# Interface_Connector.net
KiCad netlist of a schematic drawn in Altium Designer
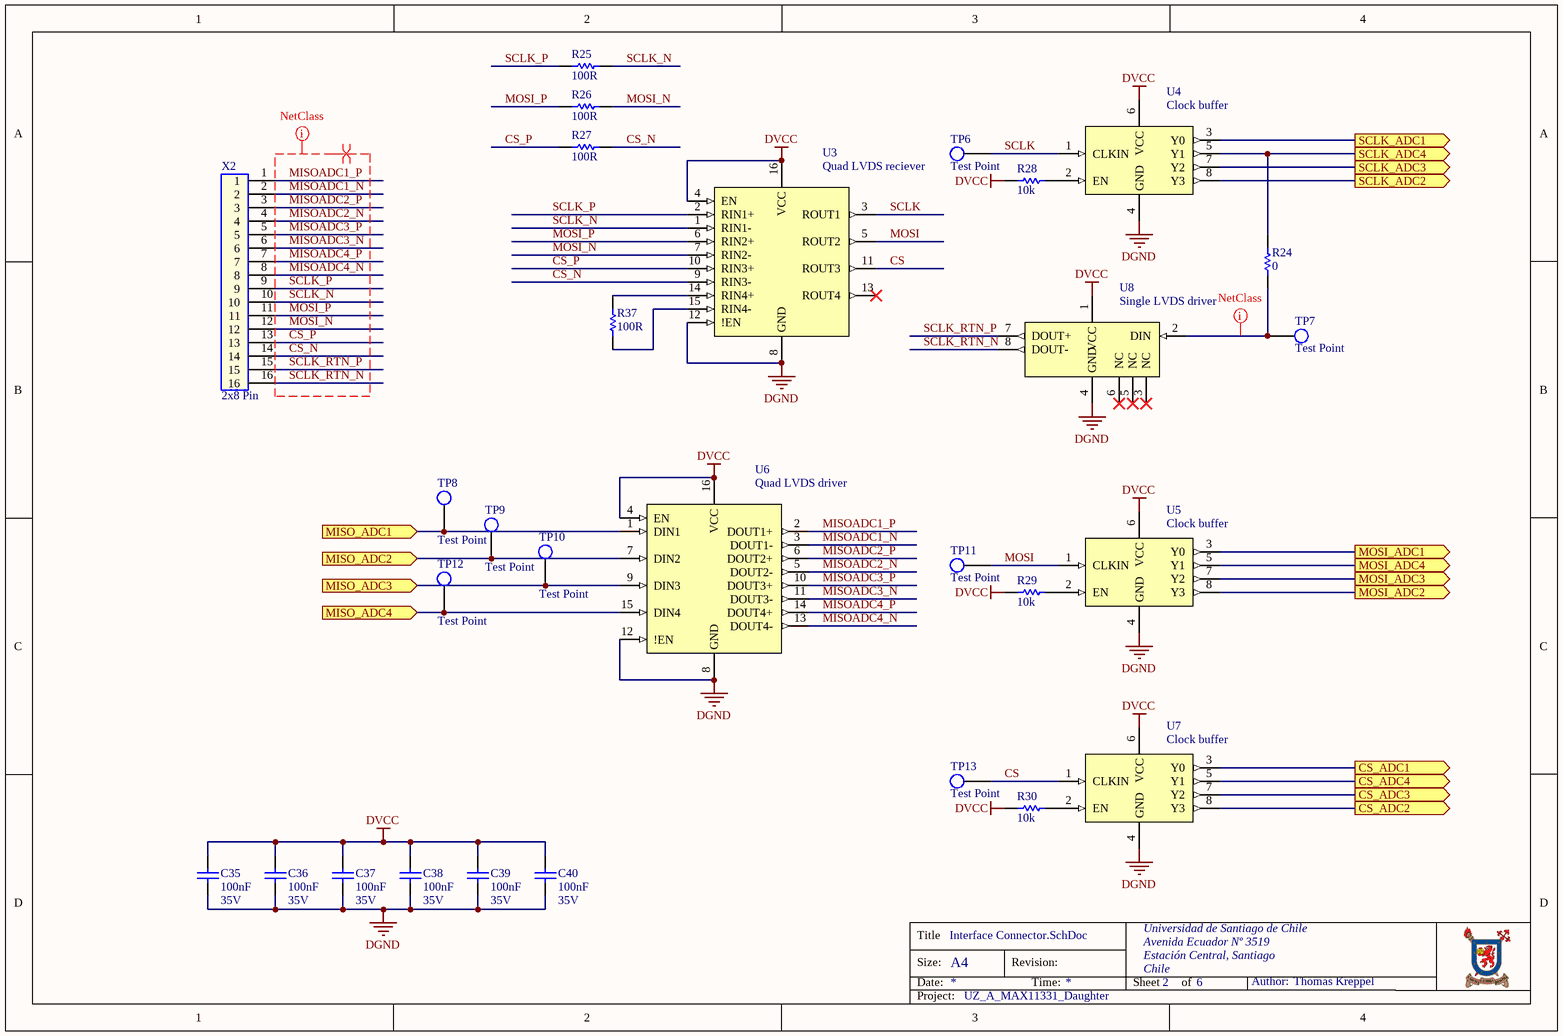
[diagram p0: Interface Connector.SchDoc]

(export (version "E")
  (design (tool "Eeschema 10.0.6"))
  (components
    (comp (ref "C35")
      (value "100nF")
      (footprint "CAP_0603")
      (description "Capacitor")
      (fields
        (field (name "MPN") "C0603C104M5RACTU")
        (field (name "MF") "KEMET")
        (field (name "VOLTAGE") "35V")
        (field (name "PUBLISHER") "Altium Limited")
      )
      (libsource (lib "Componentes_SOC") (part "Cap_0603"))
    )
    (comp (ref "C36")
      (value "100nF")
      (footprint "CAP_0603")
      (description "Capacitor")
      (fields
        (field (name "MPN") "C0603C104M5RACTU")
        (field (name "MF") "KEMET")
        (field (name "VOLTAGE") "35V")
        (field (name "PUBLISHER") "Altium Limited")
      )
      (libsource (lib "Componentes_SOC") (part "Cap_0603"))
    )
    (comp (ref "C37")
      (value "100nF")
      (footprint "CAP_0603")
      (description "Capacitor")
      (fields
        (field (name "MPN") "C0603C104M5RACTU")
        (field (name "MF") "KEMET")
        (field (name "VOLTAGE") "35V")
        (field (name "PUBLISHER") "Altium Limited")
      )
      (libsource (lib "Componentes_SOC") (part "Cap_0603"))
    )
    (comp (ref "C38")
      (value "100nF")
      (footprint "CAP_0603")
      (description "Capacitor")
      (fields
        (field (name "MPN") "C0603C104M5RACTU")
        (field (name "MF") "KEMET")
        (field (name "VOLTAGE") "35V")
        (field (name "PUBLISHER") "Altium Limited")
      )
      (libsource (lib "Componentes_SOC") (part "Cap_0603"))
    )
    (comp (ref "C39")
      (value "100nF")
      (footprint "CAP_0603")
      (description "Capacitor")
      (fields
        (field (name "MPN") "C0603C104M5RACTU")
        (field (name "MF") "KEMET")
        (field (name "VOLTAGE") "35V")
        (field (name "PUBLISHER") "Altium Limited")
      )
      (libsource (lib "Componentes_SOC") (part "Cap_0603"))
    )
    (comp (ref "C40")
      (value "100nF")
      (footprint "CAP_0603")
      (description "Capacitor")
      (fields
        (field (name "MPN") "C0603C104M5RACTU")
        (field (name "MF") "KEMET")
        (field (name "VOLTAGE") "35V")
        (field (name "PUBLISHER") "Altium Limited")
      )
      (libsource (lib "Componentes_SOC") (part "Cap_0603"))
    )
    (comp (ref "R24")
      (value "0")
      (footprint "RES_0603")
      (fields (field (name "TOLERANCE") "1%") (field (name "PUBLISHER") "Altium Limited"))
      (libsource (lib "Componentes_SOC") (part "Res0603"))
    )
    (comp (ref "R25")
      (value "100R")
      (footprint "RES_0603")
      (fields
        (field (name "MF") "Yageo")
        (field (name "MPN") "RC0603FR-07100RL")
        (field (name "TOLERANCE") "1%")
        (field (name "PUBLISHER") "Altium Limited")
      )
      (libsource (lib "Componentes_SOC") (part "Res0603"))
    )
    (comp (ref "R26")
      (value "100R")
      (footprint "RES_0603")
      (fields
        (field (name "MF") "Yageo")
        (field (name "MPN") "RC0603FR-07100RL")
        (field (name "TOLERANCE") "1%")
        (field (name "PUBLISHER") "Altium Limited")
      )
      (libsource (lib "Componentes_SOC") (part "Res0603"))
    )
    (comp (ref "R27")
      (value "100R")
      (footprint "RES_0603")
      (fields
        (field (name "MF") "Yageo")
        (field (name "MPN") "RC0603FR-07100RL")
        (field (name "TOLERANCE") "1%")
        (field (name "PUBLISHER") "Altium Limited")
      )
      (libsource (lib "Componentes_SOC") (part "Res0603"))
    )
    (comp (ref "R28")
      (value "10k")
      (footprint "RES_0603")
      (fields
        (field (name "MF") "Yageo")
        (field (name "MPN") "RC0603FR-0710KL")
        (field (name "TOLERANCE") "1%")
        (field (name "PUBLISHER") "Altium Limited")
      )
      (libsource (lib "Componentes_SOC") (part "Res0603"))
    )
    (comp (ref "R29")
      (value "10k")
      (footprint "RES_0603")
      (fields
        (field (name "MF") "Yageo")
        (field (name "MPN") "RC0603FR-0710KL")
        (field (name "TOLERANCE") "1%")
        (field (name "PUBLISHER") "Altium Limited")
      )
      (libsource (lib "Componentes_SOC") (part "Res0603"))
    )
    (comp (ref "R30")
      (value "10k")
      (footprint "RES_0603")
      (fields
        (field (name "MF") "Yageo")
        (field (name "MPN") "RC0603FR-0710KL")
        (field (name "TOLERANCE") "1%")
        (field (name "PUBLISHER") "Altium Limited")
      )
      (libsource (lib "Componentes_SOC") (part "Res0603"))
    )
    (comp (ref "R37")
      (value "100R")
      (footprint "RES_0603")
      (fields
        (field (name "MF") "Yageo")
        (field (name "MPN") "RC0603FR-07100RL")
        (field (name "TOLERANCE") "1%")
        (field (name "PUBLISHER") "Altium Limited")
      )
      (libsource (lib "Componentes_SOC") (part "Res0603"))
    )
    (comp (ref "TP6")
      (value "Test Point")
      (footprint "TP_1.6mm")
      (description "1.6mm Test Point Keystone")
      (fields
        (field (name "MF") "Keystone Electronics")
        (field (name "MPN") "5006")
        (field (name "CREATED") "2020_04_Kreppel")
      )
      (libsource (lib "Componentes_SOC") (part "TP"))
    )
    (comp (ref "TP7")
      (value "Test Point")
      (footprint "TP_1.6mm")
      (description "1.6mm Test Point Keystone")
      (fields
        (field (name "MF") "Keystone Electronics")
        (field (name "MPN") "5006")
        (field (name "CREATED") "2020_04_Kreppel")
      )
      (libsource (lib "Componentes_SOC") (part "TP"))
    )
    (comp (ref "TP8")
      (value "Test Point")
      (footprint "TP_1.6mm")
      (description "1.6mm Test Point Keystone")
      (fields
        (field (name "MF") "Keystone Electronics")
        (field (name "MPN") "5006")
        (field (name "CREATED") "2020_04_Kreppel")
      )
      (libsource (lib "Componentes_SOC") (part "TP"))
    )
    (comp (ref "TP9")
      (value "Test Point")
      (footprint "TP_1.6mm")
      (description "1.6mm Test Point Keystone")
      (fields
        (field (name "MF") "Keystone Electronics")
        (field (name "MPN") "5006")
        (field (name "CREATED") "2020_04_Kreppel")
      )
      (libsource (lib "Componentes_SOC") (part "TP"))
    )
    (comp (ref "TP10")
      (value "Test Point")
      (footprint "TP_1.6mm")
      (description "1.6mm Test Point Keystone")
      (fields
        (field (name "MF") "Keystone Electronics")
        (field (name "MPN") "5006")
        (field (name "CREATED") "2020_04_Kreppel")
      )
      (libsource (lib "Componentes_SOC") (part "TP"))
    )
    (comp (ref "TP11")
      (value "Test Point")
      (footprint "TP_1.6mm")
      (description "1.6mm Test Point Keystone")
      (fields
        (field (name "MF") "Keystone Electronics")
        (field (name "MPN") "5006")
        (field (name "CREATED") "2020_04_Kreppel")
      )
      (libsource (lib "Componentes_SOC") (part "TP"))
    )
    (comp (ref "TP12")
      (value "Test Point")
      (footprint "TP_1.6mm")
      (description "1.6mm Test Point Keystone")
      (fields
        (field (name "MF") "Keystone Electronics")
        (field (name "MPN") "5006")
        (field (name "CREATED") "2020_04_Kreppel")
      )
      (libsource (lib "Componentes_SOC") (part "TP"))
    )
    (comp (ref "TP13")
      (value "Test Point")
      (footprint "TP_1.6mm")
      (description "1.6mm Test Point Keystone")
      (fields
        (field (name "MF") "Keystone Electronics")
        (field (name "MPN") "5006")
        (field (name "CREATED") "2020_04_Kreppel")
      )
      (libsource (lib "Componentes_SOC") (part "TP"))
    )
    (comp (ref "U3")
      (value "Quad LVDS reciever")
      (footprint "TSOP65P640X120-16N")
      (description "3V, LVDS, quad, CMOS Differential Line Receiver")
      (fields
        (field (name "MF") "Analog Devices")
        (field (name "MPN") "ADN4666ARUZ")
        (field (name "CREATED") "2020_05_Kreppel")
      )
      (libsource (lib "Componentes_SOC") (part "ADN4666"))
    )
    (comp (ref "U4")
      (value "Clock buffer")
      (footprint "TSOP65P640X120-8N")
      (description "1:4 200MHz LVCMOS clock buffer, general-purpose, PCI-X Compliant")
      (fields
        (field (name "MF") "Texas Instruments")
        (field (name "MPN") "CDCV304PWRG4")
        (field (name "CREATED") "2020_05_Kreppel")
      )
      (libsource (lib "Componentes_SOC") (part "CDCV304"))
    )
    (comp (ref "U5")
      (value "Clock buffer")
      (footprint "TSOP65P640X120-8N")
      (description "1:4 200MHz LVCMOS clock buffer, general-purpose, PCI-X Compliant")
      (fields
        (field (name "MF") "Texas Instruments")
        (field (name "MPN") "CDCV304PWRG4")
        (field (name "CREATED") "2020_05_Kreppel")
      )
      (libsource (lib "Componentes_SOC") (part "CDCV304"))
    )
    (comp (ref "U6")
      (value "Quad LVDS driver")
      (footprint "TSOP65P640X120-16N")
      (description "3V, LVDS, Quad, CMOS Differential Line Driver")
      (fields
        (field (name "MF") "Analog Devices")
        (field (name "MPN") "ADN4665ARUZ")
        (field (name "CREATED") "2020_05_Kreppel")
      )
      (libsource (lib "Componentes_SOC") (part "ADN4665"))
    )
    (comp (ref "U7")
      (value "Clock buffer")
      (footprint "TSOP65P640X120-8N")
      (description "1:4 200MHz LVCMOS clock buffer, general-purpose, PCI-X Compliant")
      (fields
        (field (name "MF") "Texas Instruments")
        (field (name "MPN") "CDCV304PWRG4")
        (field (name "CREATED") "2020_05_Kreppel")
      )
      (libsource (lib "Componentes_SOC") (part "CDCV304"))
    )
    (comp (ref "U8")
      (value "Single LVDS driver")
      (footprint "SOIC127P600X170_HS-9N_no_THP")
      (description "Single, 3V, CMOS, LVDS High Speed differential driver")
      (fields
        (field (name "MF") "Analog Devices")
        (field (name "MPN") "ADN4661BRZ")
        (field (name "CREATED") "2020_05_Kreppel")
      )
      (libsource (lib "Componentes_SOC") (part "ADN4661"))
    )
    (comp (ref "X2")
      (value "2x8 Pin")
      (footprint "EHF-108-01-F-D")
      (description "Dual Row, 2x8 Shrouded IDC Header with Ejectors 50 mil pitch")
      (fields
        (field (name "MF") "Samtec")
        (field (name "MPN") "EHF-108-01-F-D")
        (field (name "CREATED") "2020_05_Kreppel")
      )
      (libsource (lib "Componentes_SOC") (part "EHF-108-01-F-D"))
    )
  )
  (nets
    (net (code "1") (name "/CS") (class "Default")
      (node (ref "TP13") (pin "1") (pinfunction "1_1") (pintype "passive"))
      (node (ref "U3") (pin "11") (pinfunction "ROUT3_11") (pintype "output"))
      (node (ref "U7") (pin "1") (pinfunction "CLKIN_1") (pintype "input"))
    )
    (net (code "2") (name "/CS_ADC1") (class "Default")
      (node (ref "U7") (pin "3") (pinfunction "Y0_3") (pintype "output"))
    )
    (net (code "3") (name "/CS_ADC2") (class "Default")
      (node (ref "U7") (pin "8") (pinfunction "Y3_8") (pintype "output"))
    )
    (net (code "4") (name "/CS_ADC3") (class "Default")
      (node (ref "U7") (pin "7") (pinfunction "Y2_7") (pintype "output"))
    )
    (net (code "5") (name "/CS_ADC4") (class "Default")
      (node (ref "U7") (pin "5") (pinfunction "Y1_5") (pintype "output"))
    )
    (net (code "6") (name "/CS_N") (class "Default")
      (node (ref "R27") (pin "1") (pinfunction "1_1") (pintype "passive"))
      (node (ref "U3") (pin "9") (pinfunction "RIN3-_9") (pintype "input"))
      (node (ref "X2") (pin "14") (pinfunction "14_14") (pintype "passive"))
    )
    (net (code "7") (name "/CS_P") (class "Default")
      (node (ref "R27") (pin "2") (pinfunction "2_2") (pintype "passive"))
      (node (ref "U3") (pin "10") (pinfunction "RIN3+_10") (pintype "input"))
      (node (ref "X2") (pin "13") (pinfunction "13_13") (pintype "passive"))
    )
    (net (code "8") (name "/MISOADC1_N") (class "Default")
      (node (ref "U6") (pin "3") (pinfunction "DOUT1-_3") (pintype "output"))
      (node (ref "X2") (pin "2") (pinfunction "2_2") (pintype "passive"))
    )
    (net (code "9") (name "/MISOADC1_P") (class "Default")
      (node (ref "U6") (pin "2") (pinfunction "DOUT1+_2") (pintype "output"))
      (node (ref "X2") (pin "1") (pinfunction "1_1") (pintype "passive"))
    )
    (net (code "10") (name "/MISOADC2_N") (class "Default")
      (node (ref "U6") (pin "5") (pinfunction "DOUT2-_5") (pintype "output"))
      (node (ref "X2") (pin "4") (pinfunction "4_4") (pintype "passive"))
    )
    (net (code "11") (name "/MISOADC2_P") (class "Default")
      (node (ref "U6") (pin "6") (pinfunction "DOUT2+_6") (pintype "output"))
      (node (ref "X2") (pin "3") (pinfunction "3_3") (pintype "passive"))
    )
    (net (code "12") (name "/MISOADC3_N") (class "Default")
      (node (ref "U6") (pin "11") (pinfunction "DOUT3-_11") (pintype "output"))
      (node (ref "X2") (pin "6") (pinfunction "6_6") (pintype "passive"))
    )
    (net (code "13") (name "/MISOADC3_P") (class "Default")
      (node (ref "U6") (pin "10") (pinfunction "DOUT3+_10") (pintype "output"))
      (node (ref "X2") (pin "5") (pinfunction "5_5") (pintype "passive"))
    )
    (net (code "14") (name "/MISOADC4_N") (class "Default")
      (node (ref "U6") (pin "13") (pinfunction "DOUT4-_13") (pintype "output"))
      (node (ref "X2") (pin "8") (pinfunction "8_8") (pintype "passive"))
    )
    (net (code "15") (name "/MISOADC4_P") (class "Default")
      (node (ref "U6") (pin "14") (pinfunction "DOUT4+_14") (pintype "output"))
      (node (ref "X2") (pin "7") (pinfunction "7_7") (pintype "passive"))
    )
    (net (code "16") (name "/MISO_ADC1") (class "Default")
      (node (ref "TP8") (pin "1") (pinfunction "1_1") (pintype "passive"))
      (node (ref "U6") (pin "1") (pinfunction "DIN1_1") (pintype "input"))
    )
    (net (code "17") (name "/MISO_ADC2") (class "Default")
      (node (ref "TP9") (pin "1") (pinfunction "1_1") (pintype "passive"))
      (node (ref "U6") (pin "7") (pinfunction "DIN2_7") (pintype "input"))
    )
    (net (code "18") (name "/MISO_ADC3") (class "Default")
      (node (ref "TP10") (pin "1") (pinfunction "1_1") (pintype "passive"))
      (node (ref "U6") (pin "9") (pinfunction "DIN3_9") (pintype "input"))
    )
    (net (code "19") (name "/MISO_ADC4") (class "Default")
      (node (ref "TP12") (pin "1") (pinfunction "1_1") (pintype "passive"))
      (node (ref "U6") (pin "15") (pinfunction "DIN4_15") (pintype "input"))
    )
    (net (code "20") (name "/MOSI") (class "Default")
      (node (ref "TP11") (pin "1") (pinfunction "1_1") (pintype "passive"))
      (node (ref "U3") (pin "5") (pinfunction "ROUT2_5") (pintype "output"))
      (node (ref "U5") (pin "1") (pinfunction "CLKIN_1") (pintype "input"))
    )
    (net (code "21") (name "/MOSI_ADC1") (class "Default")
      (node (ref "U5") (pin "3") (pinfunction "Y0_3") (pintype "output"))
    )
    (net (code "22") (name "/MOSI_ADC2") (class "Default")
      (node (ref "U5") (pin "8") (pinfunction "Y3_8") (pintype "output"))
    )
    (net (code "23") (name "/MOSI_ADC3") (class "Default")
      (node (ref "U5") (pin "7") (pinfunction "Y2_7") (pintype "output"))
    )
    (net (code "24") (name "/MOSI_ADC4") (class "Default")
      (node (ref "U5") (pin "5") (pinfunction "Y1_5") (pintype "output"))
    )
    (net (code "25") (name "/MOSI_N") (class "Default")
      (node (ref "R26") (pin "1") (pinfunction "1_1") (pintype "passive"))
      (node (ref "U3") (pin "7") (pinfunction "RIN2-_7") (pintype "input"))
      (node (ref "X2") (pin "12") (pinfunction "12_12") (pintype "passive"))
    )
    (net (code "26") (name "/MOSI_P") (class "Default")
      (node (ref "R26") (pin "2") (pinfunction "2_2") (pintype "passive"))
      (node (ref "U3") (pin "6") (pinfunction "RIN2+_6") (pintype "input"))
      (node (ref "X2") (pin "11") (pinfunction "11_11") (pintype "passive"))
    )
    (net (code "27") (name "/SCLK") (class "Default")
      (node (ref "TP6") (pin "1") (pinfunction "1_1") (pintype "passive"))
      (node (ref "U3") (pin "3") (pinfunction "ROUT1_3") (pintype "output"))
      (node (ref "U4") (pin "1") (pinfunction "CLKIN_1") (pintype "input"))
    )
    (net (code "28") (name "/SCLK_ADC1") (class "Default")
      (node (ref "U4") (pin "3") (pinfunction "Y0_3") (pintype "output"))
    )
    (net (code "29") (name "/SCLK_ADC2") (class "Default")
      (node (ref "U4") (pin "8") (pinfunction "Y3_8") (pintype "output"))
    )
    (net (code "30") (name "/SCLK_ADC3") (class "Default")
      (node (ref "U4") (pin "7") (pinfunction "Y2_7") (pintype "output"))
    )
    (net (code "31") (name "/SCLK_ADC4") (class "Default")
      (node (ref "R24") (pin "1") (pinfunction "1_1") (pintype "passive"))
      (node (ref "U4") (pin "5") (pinfunction "Y1_5") (pintype "output"))
    )
    (net (code "32") (name "/SCLK_N") (class "Default")
      (node (ref "R25") (pin "1") (pinfunction "1_1") (pintype "passive"))
      (node (ref "U3") (pin "1") (pinfunction "RIN1-_1") (pintype "input"))
      (node (ref "X2") (pin "10") (pinfunction "10_10") (pintype "passive"))
    )
    (net (code "33") (name "/SCLK_P") (class "Default")
      (node (ref "R25") (pin "2") (pinfunction "2_2") (pintype "passive"))
      (node (ref "U3") (pin "2") (pinfunction "RIN1+_2") (pintype "input"))
      (node (ref "X2") (pin "9") (pinfunction "9_9") (pintype "passive"))
    )
    (net (code "34") (name "/SCLK_RTN_N") (class "Default")
      (node (ref "U8") (pin "8") (pinfunction "DOUT-_8") (pintype "output"))
      (node (ref "X2") (pin "16") (pinfunction "16_16") (pintype "passive"))
    )
    (net (code "35") (name "/SCLK_RTN_P") (class "Default")
      (node (ref "U8") (pin "7") (pinfunction "DOUT+_7") (pintype "output"))
      (node (ref "X2") (pin "15") (pinfunction "15_15") (pintype "passive"))
    )
    (net (code "36") (name "DGND") (class "Default")
      (node (ref "C35") (pin "2") (pinfunction "2_2") (pintype "passive"))
      (node (ref "C36") (pin "2") (pinfunction "2_2") (pintype "passive"))
      (node (ref "C37") (pin "2") (pinfunction "2_2") (pintype "passive"))
      (node (ref "C38") (pin "2") (pinfunction "2_2") (pintype "passive"))
      (node (ref "C39") (pin "2") (pinfunction "2_2") (pintype "passive"))
      (node (ref "C40") (pin "2") (pinfunction "2_2") (pintype "passive"))
      (node (ref "U3") (pin "12") (pinfunction "!EN_12") (pintype "input"))
      (node (ref "U3") (pin "8") (pinfunction "GND_8") (pintype "power_in"))
      (node (ref "U4") (pin "4") (pinfunction "GND_4") (pintype "power_in"))
      (node (ref "U5") (pin "4") (pinfunction "GND_4") (pintype "power_in"))
      (node (ref "U6") (pin "12") (pinfunction "!EN_12") (pintype "input"))
      (node (ref "U6") (pin "8") (pinfunction "GND_8") (pintype "power_in"))
      (node (ref "U7") (pin "4") (pinfunction "GND_4") (pintype "power_in"))
      (node (ref "U8") (pin "4") (pinfunction "GND_4") (pintype "power_in"))
    )
    (net (code "37") (name "DVCC") (class "Default")
      (node (ref "C35") (pin "1") (pinfunction "1_1") (pintype "passive"))
      (node (ref "C36") (pin "1") (pinfunction "1_1") (pintype "passive"))
      (node (ref "C37") (pin "1") (pinfunction "1_1") (pintype "passive"))
      (node (ref "C38") (pin "1") (pinfunction "1_1") (pintype "passive"))
      (node (ref "C39") (pin "1") (pinfunction "1_1") (pintype "passive"))
      (node (ref "C40") (pin "1") (pinfunction "1_1") (pintype "passive"))
      (node (ref "R28") (pin "2") (pinfunction "2_2") (pintype "passive"))
      (node (ref "R29") (pin "2") (pinfunction "2_2") (pintype "passive"))
      (node (ref "R30") (pin "2") (pinfunction "2_2") (pintype "passive"))
      (node (ref "U3") (pin "16") (pinfunction "VCC_16") (pintype "power_in"))
      (node (ref "U3") (pin "4") (pinfunction "EN_4") (pintype "input"))
      (node (ref "U4") (pin "6") (pinfunction "VCC_6") (pintype "power_in"))
      (node (ref "U5") (pin "6") (pinfunction "VCC_6") (pintype "power_in"))
      (node (ref "U6") (pin "16") (pinfunction "VCC_16") (pintype "power_in"))
      (node (ref "U6") (pin "4") (pinfunction "EN_4") (pintype "input"))
      (node (ref "U7") (pin "6") (pinfunction "VCC_6") (pintype "power_in"))
      (node (ref "U8") (pin "1") (pinfunction "VCC_1") (pintype "power_in"))
    )
    (net (code "38") (name "Net-(U3-RIN4+)") (class "Default")
      (node (ref "R37") (pin "2") (pinfunction "2_2") (pintype "passive"))
      (node (ref "U3") (pin "14") (pinfunction "RIN4+_14") (pintype "input"))
    )
    (net (code "39") (name "Net-(U3-RIN4-)") (class "Default")
      (node (ref "R37") (pin "1") (pinfunction "1_1") (pintype "passive"))
      (node (ref "U3") (pin "15") (pinfunction "RIN4-_15") (pintype "input"))
    )
    (net (code "40") (name "Net-(U4-EN)") (class "Default")
      (node (ref "R28") (pin "1") (pinfunction "1_1") (pintype "passive"))
      (node (ref "U4") (pin "2") (pinfunction "EN_2") (pintype "input"))
    )
    (net (code "41") (name "Net-(U5-EN)") (class "Default")
      (node (ref "R29") (pin "1") (pinfunction "1_1") (pintype "passive"))
      (node (ref "U5") (pin "2") (pinfunction "EN_2") (pintype "input"))
    )
    (net (code "42") (name "Net-(U7-EN)") (class "Default")
      (node (ref "R30") (pin "1") (pinfunction "1_1") (pintype "passive"))
      (node (ref "U7") (pin "2") (pinfunction "EN_2") (pintype "input"))
    )
    (net (code "43") (name "Net-(U8-DIN)") (class "Default")
      (node (ref "R24") (pin "2") (pinfunction "2_2") (pintype "passive"))
      (node (ref "TP7") (pin "1") (pinfunction "1_1") (pintype "passive"))
      (node (ref "U8") (pin "2") (pinfunction "DIN_2") (pintype "input"))
    )
    (net (code "44") (name "unconnected-(U3-ROUT4-Pad13)") (class "Default")
      (node (ref "U3") (pin "13") (pinfunction "ROUT4_13") (pintype "output+no_connect"))
    )
    (net (code "45") (name "unconnected-(U8-NC-Pad3)") (class "Default")
      (node (ref "U8") (pin "3") (pinfunction "NC_3") (pintype "passive+no_connect"))
    )
    (net (code "46") (name "unconnected-(U8-NC-Pad5)") (class "Default")
      (node (ref "U8") (pin "5") (pinfunction "NC_5") (pintype "passive+no_connect"))
    )
    (net (code "47") (name "unconnected-(U8-NC-Pad6)") (class "Default")
      (node (ref "U8") (pin "6") (pinfunction "NC_6") (pintype "passive+no_connect"))
    )
  )
)
